# iod-node.net
KiCad netlist of a schematic drawn in EAGLE
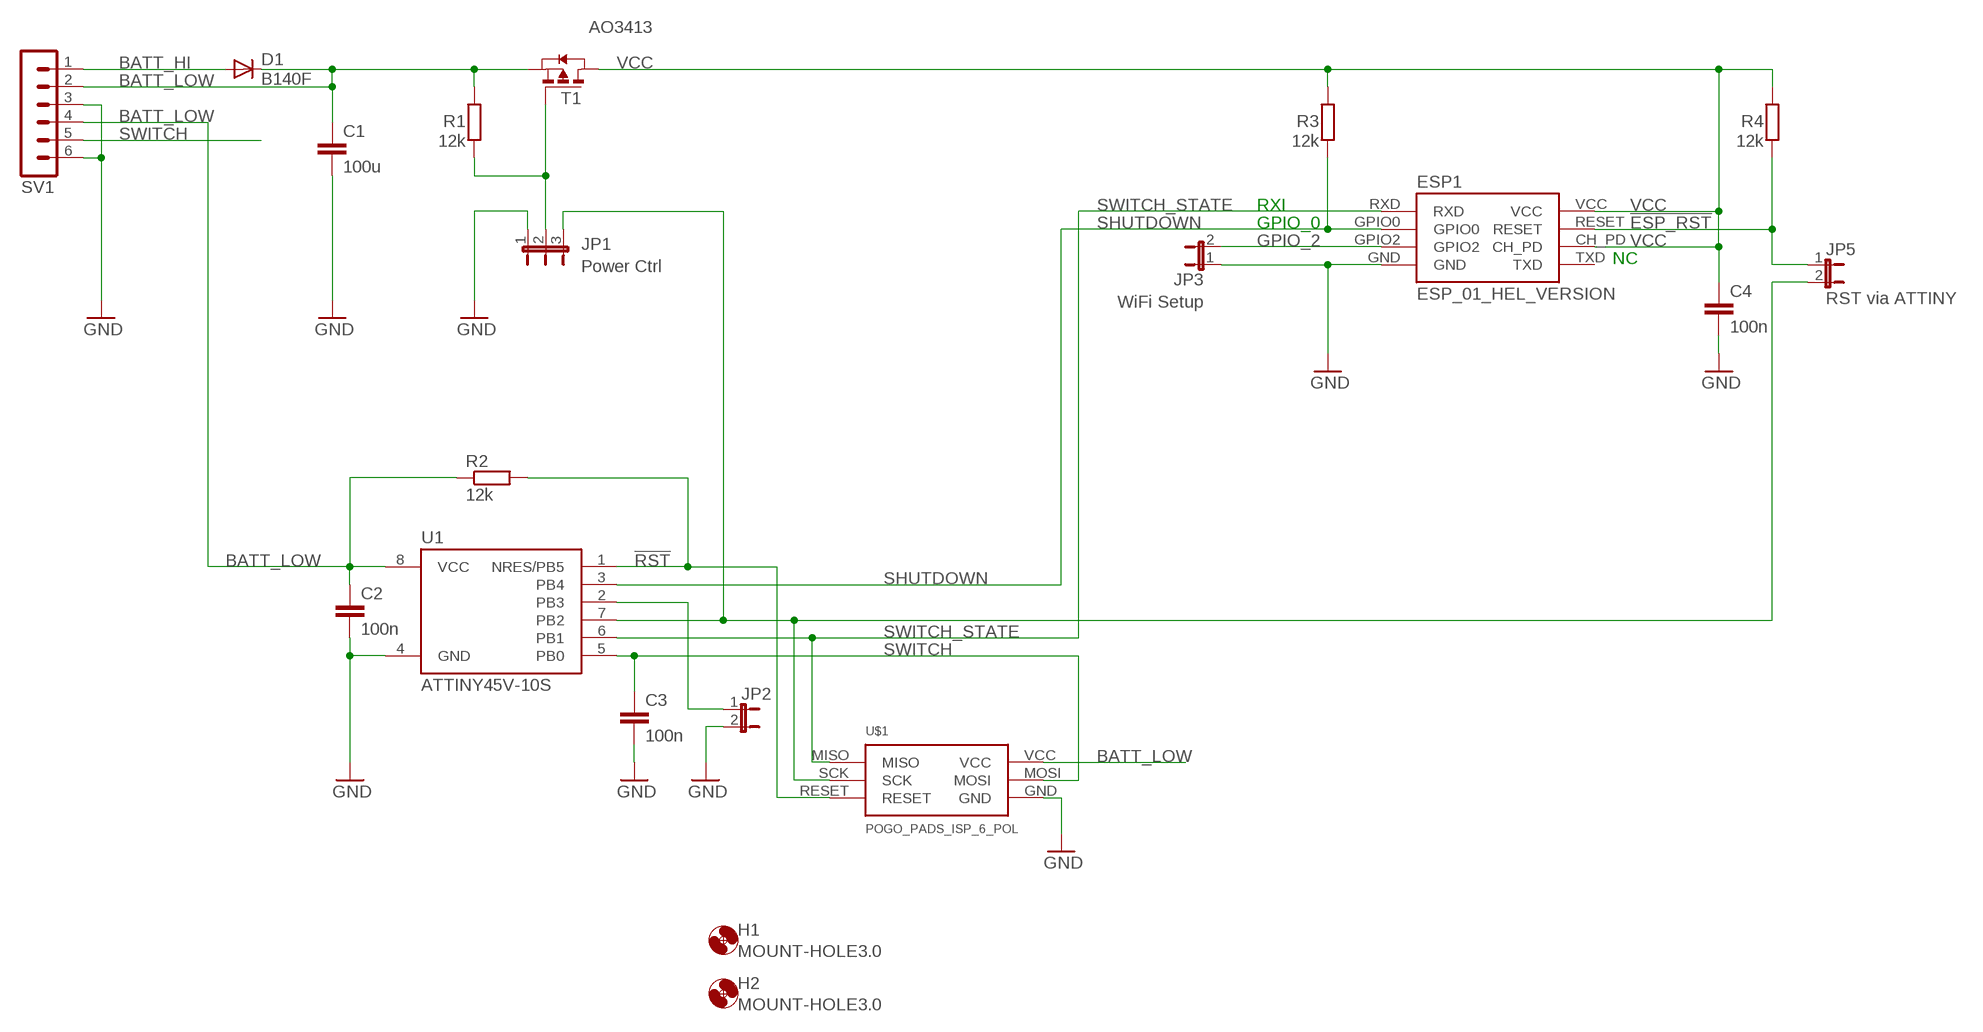
[diagram p0: schematic, sheet 1]

(export (version "E")
  (design (tool "Eeschema 10.0.6"))
  (components
    (comp (ref "C1")
      (value "100u")
      (footprint "eagle-import:C1210")
      (libsource (lib "eagle-import") (part "C-EUC1210"))
    )
    (comp (ref "C2")
      (value "100n")
      (footprint "eagle-import:C3225")
      (libsource (lib "eagle-import") (part "C-EUC3225"))
    )
    (comp (ref "C3")
      (value "100n")
      (footprint "eagle-import:C3225")
      (libsource (lib "eagle-import") (part "C-EUC3225"))
    )
    (comp (ref "C4")
      (value "100n")
      (footprint "eagle-import:C3225")
      (libsource (lib "eagle-import") (part "C-EUC3225"))
    )
    (comp (ref "D1")
      (value "B140F")
      (footprint "eagle-import:DO214AA")
      (libsource (lib "eagle-import") (part "DIODE-DO214AA"))
    )
    (comp (ref "ESP1")
      (value "ESP_01_HEL_VERSION")
      (footprint "eagle-import:CUSTOM_ESP01_FOR_HEL")
      (libsource (lib "eagle-import") (part "ESP_01_HEL_VERSION"))
    )
    (comp (ref "H1")
      (value "MOUNT-HOLE3.0")
      (footprint "eagle-import:3,0")
      (libsource (lib "eagle-import") (part "MOUNT-HOLE3.0"))
    )
    (comp (ref "H2")
      (value "MOUNT-HOLE3.0")
      (footprint "eagle-import:3,0")
      (libsource (lib "eagle-import") (part "MOUNT-HOLE3.0"))
    )
    (comp (ref "JP1")
      (value "Power Ctrl")
      (footprint "eagle-import:JP2")
      (libsource (lib "eagle-import") (part "JP2E"))
    )
    (comp (ref "JP2")
      (value "JP1E")
      (footprint "eagle-import:JP1")
      (libsource (lib "eagle-import") (part "JP1E"))
    )
    (comp (ref "JP3")
      (value "WiFi Setup")
      (footprint "eagle-import:JP1")
      (libsource (lib "eagle-import") (part "JP1E"))
    )
    (comp (ref "JP5")
      (value "RST via ATTINY")
      (footprint "eagle-import:JP1")
      (libsource (lib "eagle-import") (part "JP1E"))
    )
    (comp (ref "R1")
      (value "12k")
      (footprint "eagle-import:R0805")
      (libsource (lib "eagle-import") (part "R-EU_R0805"))
    )
    (comp (ref "R2")
      (value "12k")
      (footprint "eagle-import:R0805")
      (libsource (lib "eagle-import") (part "R-EU_R0805"))
    )
    (comp (ref "R3")
      (value "12k")
      (footprint "eagle-import:R0805")
      (libsource (lib "eagle-import") (part "R-EU_R0805"))
    )
    (comp (ref "R4")
      (value "12k")
      (footprint "eagle-import:R0805")
      (libsource (lib "eagle-import") (part "R-EU_R0805"))
    )
    (comp (ref "SV1")
      (value "MA06-1")
      (footprint "eagle-import:MA06-1")
      (libsource (lib "eagle-import") (part "MA06-1"))
    )
    (comp (ref "T1")
      (value "AO3413")
      (footprint "eagle-import:SOT-23")
      (libsource (lib "eagle-import") (part "PMOSSOT23"))
    )
    (comp (ref "U$1")
      (value "POGO_PADS_ISP_6_POL")
      (footprint "eagle-import:POGO_PADS_ISP_6_POL")
      (libsource (lib "eagle-import") (part "POGO_PADS_ISP_6_POL"))
    )
    (comp (ref "U1")
      (value "ATTINY45V-10S")
      (footprint "eagle-import:SOIC8_EIAJ_208MIL")
      (libsource (lib "eagle-import") (part "ATTINY45SV-10"))
    )
  )
  (nets
    (net (code "1") (name "/BATT_HI") (class "Default")
      (node (ref "D1") (pin "A") (pinfunction "A_A") (pintype "passive"))
      (node (ref "SV1") (pin "1") (pinfunction "1_1") (pintype "passive"))
    )
    (net (code "2") (name "/BATT_LOW") (class "Default")
      (node (ref "C1") (pin "1") (pinfunction "1_1") (pintype "passive"))
      (node (ref "C2") (pin "1") (pinfunction "1_1") (pintype "passive"))
      (node (ref "D1") (pin "C") (pinfunction "C_C") (pintype "passive"))
      (node (ref "R1") (pin "2") (pinfunction "2_2") (pintype "passive"))
      (node (ref "R2") (pin "1") (pinfunction "1_1") (pintype "passive"))
      (node (ref "SV1") (pin "2") (pinfunction "2_2") (pintype "passive"))
      (node (ref "SV1") (pin "4") (pinfunction "4_4") (pintype "passive"))
      (node (ref "T1") (pin "2") (pinfunction "S_2") (pintype "passive"))
      (node (ref "U$1") (pin "VCC") (pinfunction "VCC_VCC") (pintype "bidirectional"))
      (node (ref "U1") (pin "8") (pinfunction "VCC_8") (pintype "power_in"))
    )
    (net (code "3") (name "/GPIO_2") (class "Default")
      (node (ref "ESP1") (pin "GPIO2") (pinfunction "GPIO2_GPIO2") (pintype "bidirectional"))
      (node (ref "JP3") (pin "2") (pinfunction "2_2") (pintype "passive"))
    )
    (net (code "4") (name "/SHUTDOWN") (class "Default")
      (node (ref "ESP1") (pin "GPIO0") (pinfunction "GPIO0_GPIO0") (pintype "bidirectional"))
      (node (ref "R3") (pin "1") (pinfunction "1_1") (pintype "passive"))
      (node (ref "U1") (pin "3") (pinfunction "PB4_3") (pintype "bidirectional"))
    )
    (net (code "5") (name "/SWITCH") (class "Default")
      (node (ref "C3") (pin "1") (pinfunction "1_1") (pintype "passive"))
      (node (ref "SV1") (pin "5") (pinfunction "5_5") (pintype "passive"))
      (node (ref "U$1") (pin "MOSI") (pinfunction "MOSI_MOSI") (pintype "bidirectional"))
      (node (ref "U1") (pin "5") (pinfunction "PB0_5") (pintype "bidirectional"))
    )
    (net (code "6") (name "/SWITCH_STATE") (class "Default")
      (node (ref "ESP1") (pin "RXD") (pinfunction "RXD_RXD") (pintype "bidirectional"))
      (node (ref "U$1") (pin "MISO") (pinfunction "MISO_MISO") (pintype "bidirectional"))
      (node (ref "U1") (pin "6") (pinfunction "PB1_6") (pintype "bidirectional"))
    )
    (net (code "7") (name "/VCC") (class "Default")
      (node (ref "C4") (pin "1") (pinfunction "1_1") (pintype "passive"))
      (node (ref "ESP1") (pin "CH_PD") (pinfunction "CH_PD_CH_PD") (pintype "bidirectional"))
      (node (ref "ESP1") (pin "VCC") (pinfunction "VCC_VCC") (pintype "bidirectional"))
      (node (ref "R3") (pin "2") (pinfunction "2_2") (pintype "passive"))
      (node (ref "R4") (pin "2") (pinfunction "2_2") (pintype "passive"))
      (node (ref "T1") (pin "1") (pinfunction "D_1") (pintype "passive"))
    )
    (net (code "8") (name "/~{ESP_RST}") (class "Default")
      (node (ref "ESP1") (pin "RESET") (pinfunction "RESET_RESET") (pintype "bidirectional"))
      (node (ref "JP5") (pin "1") (pinfunction "1_1") (pintype "passive"))
      (node (ref "R4") (pin "1") (pinfunction "1_1") (pintype "passive"))
    )
    (net (code "9") (name "/~{RST}") (class "Default")
      (node (ref "R2") (pin "2") (pinfunction "2_2") (pintype "passive"))
      (node (ref "U$1") (pin "RESET") (pinfunction "RESET_RESET") (pintype "bidirectional"))
      (node (ref "U1") (pin "1") (pinfunction "NRES/PB5_1") (pintype "bidirectional"))
    )
    (net (code "10") (name "GND") (class "Default")
      (node (ref "C1") (pin "2") (pinfunction "2_2") (pintype "passive"))
      (node (ref "C2") (pin "2") (pinfunction "2_2") (pintype "passive"))
      (node (ref "C3") (pin "2") (pinfunction "2_2") (pintype "passive"))
      (node (ref "C4") (pin "2") (pinfunction "2_2") (pintype "passive"))
      (node (ref "ESP1") (pin "GND") (pinfunction "GND_GND") (pintype "bidirectional"))
      (node (ref "JP1") (pin "1") (pinfunction "1_1") (pintype "passive"))
      (node (ref "JP2") (pin "2") (pinfunction "2_2") (pintype "passive"))
      (node (ref "JP3") (pin "1") (pinfunction "1_1") (pintype "passive"))
      (node (ref "SV1") (pin "3") (pinfunction "3_3") (pintype "passive"))
      (node (ref "SV1") (pin "6") (pinfunction "6_6") (pintype "passive"))
      (node (ref "U$1") (pin "GND") (pinfunction "GND_GND") (pintype "bidirectional"))
      (node (ref "U1") (pin "4") (pinfunction "GND_4") (pintype "power_in"))
    )
    (net (code "11") (name "Net-(T1-G)") (class "Default")
      (node (ref "JP1") (pin "2") (pinfunction "2_2") (pintype "passive"))
      (node (ref "R1") (pin "1") (pinfunction "1_1") (pintype "passive"))
      (node (ref "T1") (pin "3") (pinfunction "G_3") (pintype "passive"))
    )
    (net (code "12") (name "Net-(U1-PB2)") (class "Default")
      (node (ref "JP1") (pin "3") (pinfunction "3_3") (pintype "passive"))
      (node (ref "JP5") (pin "2") (pinfunction "2_2") (pintype "passive"))
      (node (ref "U$1") (pin "SCK") (pinfunction "SCK_SCK") (pintype "bidirectional"))
      (node (ref "U1") (pin "7") (pinfunction "PB2_7") (pintype "bidirectional"))
    )
    (net (code "13") (name "Net-(U1-PB3)") (class "Default")
      (node (ref "JP2") (pin "1") (pinfunction "1_1") (pintype "passive"))
      (node (ref "U1") (pin "2") (pinfunction "PB3_2") (pintype "bidirectional"))
    )
    (net (code "14") (name "unconnected-(ESP1-PadTXD)") (class "Default")
      (node (ref "ESP1") (pin "TXD") (pinfunction "TXD_TXD") (pintype "bidirectional"))
    )
  )
)
